# IP5568-MCU-188-3LED-ACL-V1_0.net
KiCad netlist of a schematic drawn in Altium Designer
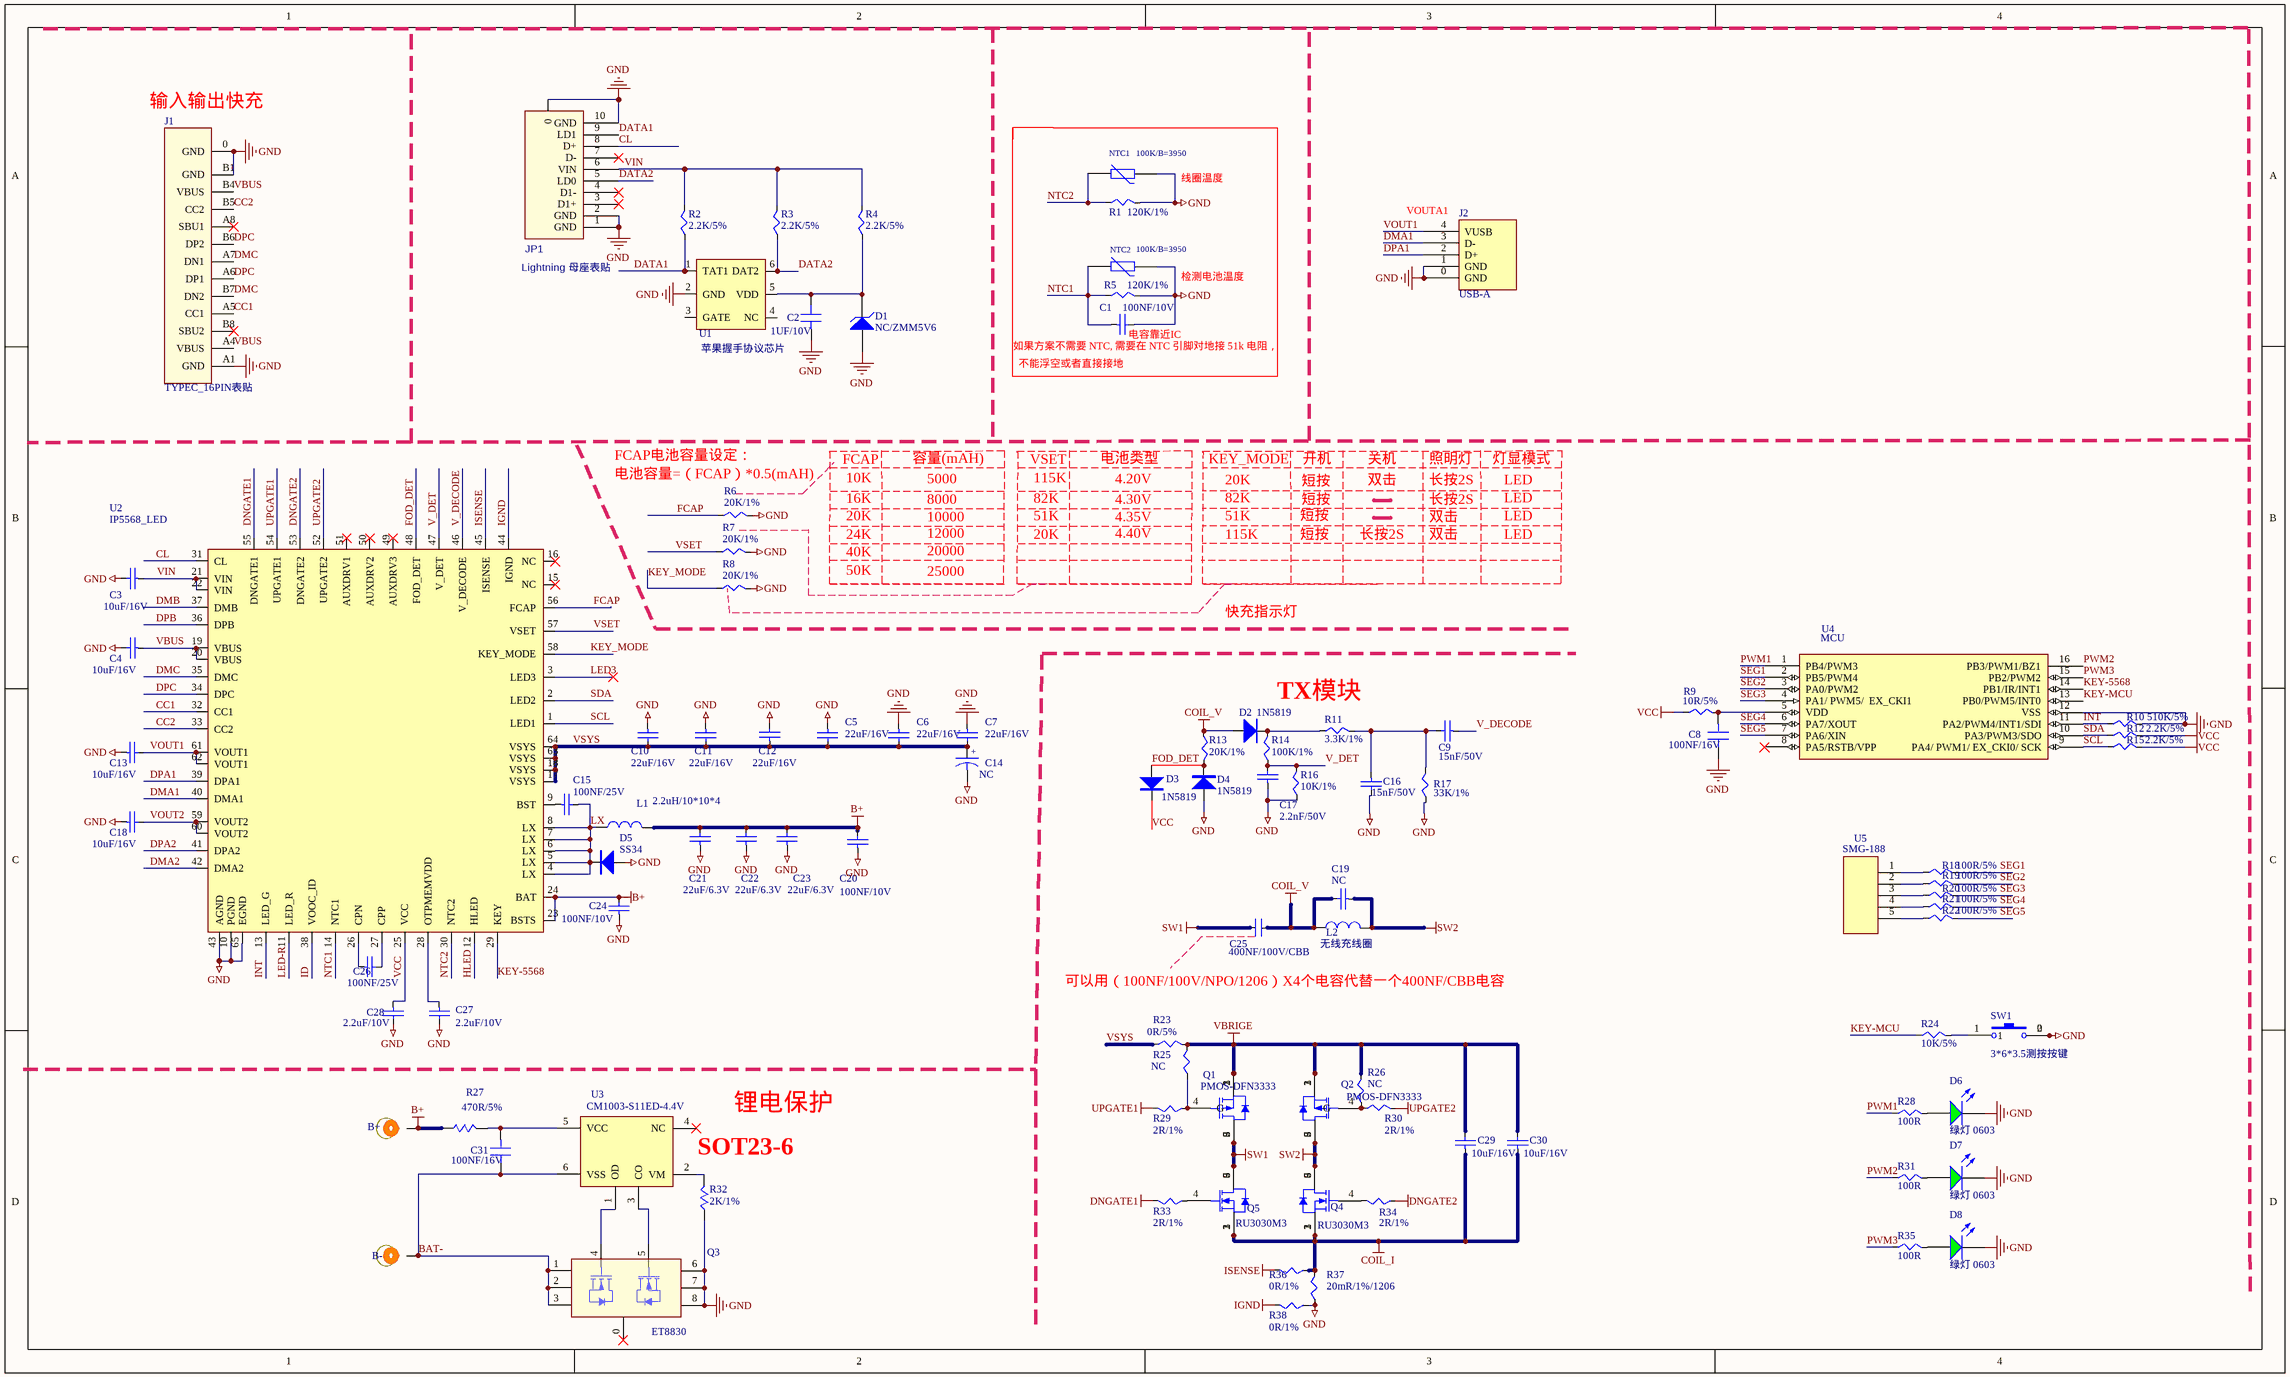
[diagram p0: IP5568-MCU-188-3LED-ACL-V1.0.SchDoc]

(export (version "E")
  (design (tool "Eeschema 10.0.6"))
  (components
    (comp (ref "B+")
      (value "BAT+")
      (footprint "BAT-3X3")
      (libsource (lib "nagg_zhang20201228") (part "BAT+"))
    )
    (comp (ref "B-")
      (value "BAT-")
      (footprint "BAT-3X3")
      (libsource (lib "nagg_zhang20201228") (part "BAT-"))
    )
    (comp (ref "C1")
      (value "100NF/10V")
      (footprint "0402C")
      (description "Capacitor")
      (libsource (lib "A") (part "CAP"))
    )
    (comp (ref "C2")
      (value "1UF/10V")
      (footprint "0402C")
      (libsource (lib "nagg_zhang20201228") (part "CAP-0603"))
    )
    (comp (ref "C3")
      (value "10uF/16V")
      (footprint "C0805")
      (description "Capacitor")
      (libsource (lib "A") (part "CAP"))
    )
    (comp (ref "C4")
      (value "10uF/16V")
      (footprint "C0805")
      (description "Capacitor")
      (libsource (lib "A") (part "CAP"))
    )
    (comp (ref "C5")
      (value "22uF/16V")
      (footprint "C0805")
      (description "Capacitor")
      (libsource (lib "A") (part "CAP"))
    )
    (comp (ref "C6")
      (value "22uF/16V")
      (footprint "C0805")
      (description "Capacitor")
      (libsource (lib "A") (part "CAP"))
    )
    (comp (ref "C7")
      (value "22uF/16V")
      (footprint "C0805")
      (description "Capacitor")
      (libsource (lib "A") (part "CAP"))
    )
    (comp (ref "C8")
      (value "100NF/16V")
      (footprint "0402C")
      (libsource (lib "nagg_zhang20201228") (part "CAP-0603"))
    )
    (comp (ref "C9")
      (value "15nF/50V")
      (footprint "0402C")
      (description "Capacitor")
      (libsource (lib "A") (part "CAP"))
    )
    (comp (ref "C10")
      (value "22uF/16V")
      (footprint "C0805")
      (description "Capacitor")
      (libsource (lib "A") (part "CAP"))
    )
    (comp (ref "C11")
      (value "22uF/16V")
      (footprint "C0805")
      (description "Capacitor")
      (libsource (lib "A") (part "CAP"))
    )
    (comp (ref "C12")
      (value "22uF/16V")
      (footprint "C0805")
      (description "Capacitor")
      (libsource (lib "A") (part "CAP"))
    )
    (comp (ref "C13")
      (value "10uF/16V")
      (footprint "C0805")
      (description "Capacitor")
      (libsource (lib "A") (part "CAP"))
    )
    (comp (ref "C14")
      (value "NC")
      (footprint "CAP-6.3X8-P2.5-S1")
      (description "Capacitor")
      (libsource (lib "A") (part "CAPACITOR POL"))
    )
    (comp (ref "C15")
      (value "100NF/25V")
      (footprint "0402C")
      (description "Capacitor")
      (libsource (lib "A") (part "CAP"))
    )
    (comp (ref "C16")
      (value "15nF/50V")
      (footprint "0402C")
      (description "Capacitor")
      (libsource (lib "A") (part "CAP"))
    )
    (comp (ref "C17")
      (value "2.2nF/50V")
      (footprint "0402C")
      (description "Capacitor")
      (libsource (lib "A") (part "CAP"))
    )
    (comp (ref "C18")
      (value "10uF/16V")
      (footprint "C0805")
      (description "Capacitor")
      (libsource (lib "A") (part "CAP"))
    )
    (comp (ref "C19")
      (value "NC")
      (footprint "0402C")
      (description "Capacitor")
      (libsource (lib "A") (part "CAP"))
    )
    (comp (ref "C20")
      (value "100NF/10V")
      (footprint "0402C")
      (description "Capacitor")
      (libsource (lib "A") (part "CAP"))
    )
    (comp (ref "C21")
      (value "22uF/6.3V")
      (footprint "C0805")
      (description "Capacitor")
      (libsource (lib "A") (part "CAP"))
    )
    (comp (ref "C22")
      (value "22uF/6.3V")
      (footprint "C0805")
      (description "Capacitor")
      (libsource (lib "A") (part "CAP"))
    )
    (comp (ref "C23")
      (value "22uF/6.3V")
      (footprint "C0805")
      (description "Capacitor")
      (libsource (lib "A") (part "CAP"))
    )
    (comp (ref "C24")
      (value "100NF/10V")
      (footprint "0402C")
      (description "Capacitor")
      (libsource (lib "A") (part "CAP"))
    )
    (comp (ref "C25")
      (value "400NF/100V/CBB")
      (footprint "CAP-CBB-404 100V")
      (description "Capacitor")
      (libsource (lib "") (part "CAP_1"))
    )
    (comp (ref "C26")
      (value "100NF/25V")
      (footprint "0402C")
      (description "Capacitor")
      (libsource (lib "A") (part "CAP"))
    )
    (comp (ref "C27")
      (value "2.2uF/10V")
      (footprint "0603C")
      (description "Capacitor")
      (libsource (lib "A") (part "CAP"))
    )
    (comp (ref "C28")
      (value "2.2uF/10V")
      (footprint "0603C")
      (description "Capacitor")
      (libsource (lib "A") (part "CAP"))
    )
    (comp (ref "C29")
      (value "10uF/16V")
      (footprint "C0805")
      (description "Capacitor")
      (libsource (lib "A") (part "CAP"))
    )
    (comp (ref "C30")
      (value "10uF/16V")
      (footprint "C0805")
      (description "Capacitor")
      (libsource (lib "A") (part "CAP"))
    )
    (comp (ref "C31")
      (value "100NF/16V")
      (footprint "0402C")
      (libsource (lib "nagg_zhang20201228") (part "CAP-0603"))
    )
    (comp (ref "D1")
      (value "NC/ZMM5V6")
      (footprint "SOD-123")
      (description "稳压二极管")
      (libsource (lib "Zener") (part "LL-34 ZMM5V6"))
    )
    (comp (ref "D2")
      (value "1N5819")
      (footprint "SOD-323")
      (description "Diode")
      (libsource (lib "A") (part "DIODE"))
    )
    (comp (ref "D3")
      (value "1N5819")
      (footprint "SOD-323")
      (description "Diode")
      (libsource (lib "A") (part "DIODE"))
    )
    (comp (ref "D4")
      (value "1N5819")
      (footprint "SOD-323")
      (description "Diode")
      (libsource (lib "A") (part "DIODE"))
    )
    (comp (ref "D5")
      (value "SS34")
      (footprint "SMA")
      (description "Diode")
      (libsource (lib "") (part "DIODE_1"))
    )
    (comp (ref "D6")
      (value "绿灯 0603")
      (footprint "LC-0603_LED_S1")
      (description "发光二极管")
      (libsource (lib "LED") (part "0603 绿灯"))
    )
    (comp (ref "D7")
      (value "绿灯 0603")
      (footprint "LC-0603_LED_S1")
      (description "发光二极管")
      (libsource (lib "LED") (part "0603 绿灯"))
    )
    (comp (ref "D8")
      (value "绿灯 0603")
      (footprint "LC-0603_LED_S1")
      (description "发光二极管")
      (libsource (lib "LED") (part "0603 绿灯"))
    )
    (comp (ref "J1")
      (value "TYPEC_16PIN表贴")
      (footprint "TYPE C 2.0-16pin 表贴")
      (libsource (lib "AD09-POWER BANK") (part "TYPEC_16PIN表贴"))
    )
    (comp (ref "J2")
      (value "USB-A")
      (footprint "USB-AF8.5沉板1.9前插后贴")
      (libsource (lib "AD09-POWER BANK") (part "USB--A-4PIN"))
    )
    (comp (ref "JP1")
      (value "Lightning 母座表贴")
      (footprint "Lightning_10")
      (libsource (lib "AD09-POWER BANK") (part "Lightning 母座表贴"))
    )
    (comp (ref "L1")
      (value "2.2uH/10*10*4")
      (footprint "L1040")
      (description "电感")
      (libsource (lib "A") (part "INDUCTOR"))
    )
    (comp (ref "L2")
      (value "无线充线圈")
      (footprint "2P-2.5L")
      (description "电感")
      (libsource (lib "A") (part "INDUCTOR"))
    )
    (comp (ref "NTC1")
      (value "100K/B=3950")
      (footprint "NTC-插件")
      (description "温敏电阻")
      (libsource (lib "AD09-POWER BANK") (part "NTC"))
    )
    (comp (ref "NTC2")
      (value "100K/B=3950")
      (footprint "NTC-插件")
      (description "温敏电阻")
      (libsource (lib "AD09-POWER BANK") (part "NTC"))
    )
    (comp (ref "Q1")
      (value "PMOS-DFN3333")
      (footprint "PDFN3333-8_L3.1-W3.2-P0.65-LS3.4-BL")
      (libsource (lib "AD09-POWER BANK") (part "PMOS-DFN3333_1"))
    )
    (comp (ref "Q2")
      (value "PMOS-DFN3333")
      (footprint "PDFN3333-8_L3.1-W3.2-P0.65-LS3.4-BL")
      (libsource (lib "AD09-POWER BANK") (part "PMOS-DFN3333_1"))
    )
    (comp (ref "Q3")
      (value "ET8830")
      (footprint "ET-8830-DFN3x3-8L")
      (description "NMOS-DUAL-N")
      (libsource (lib "AD09-POWER BANK") (part "NMOS-ET8830-DFN3333"))
    )
    (comp (ref "Q4")
      (value "RU3030M3")
      (footprint "PDFN3333-8_L3.1-W3.2-P0.65-LS3.4-BL")
      (description "NMOS-DFN3333")
      (libsource (lib "AD09-POWER BANK") (part "NMOS-DFN3333"))
    )
    (comp (ref "Q5")
      (value "RU3030M3")
      (footprint "PDFN3333-8_L3.1-W3.2-P0.65-LS3.4-BL")
      (description "NMOS-DFN3333")
      (libsource (lib "AD09-POWER BANK") (part "NMOS-DFN3333"))
    )
    (comp (ref "R1") (value "120K/1%") (footprint "0402R") (libsource (lib "A") (part "RES1")))
    (comp (ref "R2") (value "2.2K/5%") (footprint "0402R") (libsource (lib "A") (part "RES1")))
    (comp (ref "R3") (value "2.2K/5%") (footprint "0402R") (libsource (lib "A") (part "RES1")))
    (comp (ref "R4") (value "2.2K/5%") (footprint "0402R") (libsource (lib "A") (part "RES1")))
    (comp (ref "R5") (value "120K/1%") (footprint "0402R") (libsource (lib "A") (part "RES1")))
    (comp (ref "R6") (value "20K/1%") (footprint "0402R") (libsource (lib "A") (part "RES1")))
    (comp (ref "R7") (value "20K/1%") (footprint "0402R") (libsource (lib "A") (part "RES1")))
    (comp (ref "R8") (value "20K/1%") (footprint "0402R") (libsource (lib "A") (part "RES1")))
    (comp (ref "R9") (value "10R/5%") (footprint "0603R") (libsource (lib "A") (part "RES1")))
    (comp (ref "R10") (value "510K/5%") (footprint "0402R") (libsource (lib "A") (part "RES1")))
    (comp (ref "R11") (value "3.3K/1%") (footprint "0402R") (libsource (lib "A") (part "RES1")))
    (comp (ref "R12") (value "2.2K/5%") (footprint "0402R") (libsource (lib "A") (part "RES1")))
    (comp (ref "R13") (value "20K/1%") (footprint "0402R") (libsource (lib "A") (part "RES1")))
    (comp (ref "R14") (value "100K/1%") (footprint "0402R") (libsource (lib "A") (part "RES1")))
    (comp (ref "R15") (value "2.2K/5%") (footprint "0402R") (libsource (lib "A") (part "RES1")))
    (comp (ref "R16") (value "10K/1%") (footprint "0402R") (libsource (lib "A") (part "RES1")))
    (comp (ref "R17") (value "33K/1%") (footprint "0402R") (libsource (lib "A") (part "RES1")))
    (comp (ref "R18") (value "100R/5%") (footprint "0402R") (libsource (lib "A") (part "RES1")))
    (comp (ref "R19") (value "100R/5%") (footprint "0402R") (libsource (lib "A") (part "RES1")))
    (comp (ref "R20") (value "100R/5%") (footprint "0402R") (libsource (lib "A") (part "RES1")))
    (comp (ref "R21") (value "100R/5%") (footprint "0402R") (libsource (lib "A") (part "RES1")))
    (comp (ref "R22") (value "100R/5%") (footprint "0402R") (libsource (lib "A") (part "RES1")))
    (comp (ref "R23") (value "0R/5%") (footprint "0805") (libsource (lib "A") (part "RES1")))
    (comp (ref "R24") (value "10K/5%") (footprint "0402R") (libsource (lib "A") (part "RES1")))
    (comp (ref "R25") (value "NC") (footprint "0402R") (libsource (lib "A") (part "RES1")))
    (comp (ref "R26") (value "NC") (footprint "0402R") (libsource (lib "A") (part "RES1")))
    (comp (ref "R27")
      (value "470R/5%")
      (footprint "0402R")
      (libsource (lib "nagg_zhang20201228") (part "RES-0603"))
    )
    (comp (ref "R28") (value "100R") (footprint "0402R") (libsource (lib "A") (part "RES1")))
    (comp (ref "R29") (value "2R/1%") (footprint "0402R") (libsource (lib "A") (part "RES1")))
    (comp (ref "R30") (value "2R/1%") (footprint "0402R") (libsource (lib "A") (part "RES1")))
    (comp (ref "R31") (value "100R") (footprint "0402R") (libsource (lib "A") (part "RES1")))
    (comp (ref "R32")
      (value "2K/1%")
      (footprint "0402R")
      (libsource (lib "nagg_zhang20201228") (part "RES-0603"))
    )
    (comp (ref "R33") (value "2R/1%") (footprint "0402R") (libsource (lib "A") (part "RES1")))
    (comp (ref "R34") (value "2R/1%") (footprint "0402R") (libsource (lib "A") (part "RES1")))
    (comp (ref "R35") (value "100R") (footprint "0402R") (libsource (lib "A") (part "RES1")))
    (comp (ref "R36") (value "0R/1%") (footprint "0402R") (libsource (lib "A") (part "RES1")))
    (comp (ref "R37") (value "20mR/1%/1206") (footprint "1206") (libsource (lib "A") (part "RES1")))
    (comp (ref "R38") (value "0R/1%") (footprint "0402R") (libsource (lib "A") (part "RES1")))
    (comp (ref "SW1")
      (value "3*6*3.5测按按键")
      (footprint "SW-3X6X3.5mm-定位柱0.7-通孔")
      (description "侧按按键")
      (fields (field (name "PUBLISHER") "Altium Limited"))
      (libsource (lib "AD09-POWER BANK") (part "KEY-3*6*3.5mm"))
    )
    (comp (ref "U1") (value "苹果握手协议芯片") (footprint "SOT23-6") (libsource (lib "A") (part "LP05")))
    (comp (ref "U2")
      (value "IP5568_LED")
      (footprint "QFN64-8*8-0.4")
      (description "移动电源快充+无线充快充TX/RX")
      (libsource (lib "A") (part "IP5568"))
    )
    (comp (ref "U3")
      (value "CM1003-S11ED-4.4V")
      (footprint "SOT23-6")
      (description "锂电保护芯片")
      (libsource (lib "AD09-POWER BANK") (part "CM1003"))
    )
    (comp (ref "U4")
      (value "MCU")
      (footprint "SOP16L")
      (libsource (lib "AD09-POWER BANK") (part "MCU_NY8A054E"))
    )
    (comp (ref "U5")
      (value "SMG-188")
      (footprint "SMG-188-CYZ2342-5-75BWGD")
      (libsource (lib "AD09-POWER BANK") (part "SMG-188-YFT1508SWPGAD-5D-1"))
    )
  )
  (nets
    (net (code "1") (name "/BAT-") (class "Default")
      (node (ref "B-") (pin "1") (pinfunction "1_1") (pintype "passive"))
      (node (ref "C31") (pin "2") (pinfunction "2_2") (pintype "passive"))
      (node (ref "Q3") (pin "1") (pinfunction "S1_1") (pintype "passive"))
      (node (ref "Q3") (pin "2") (pinfunction "S1_2") (pintype "passive"))
      (node (ref "Q3") (pin "3") (pinfunction "S1_3") (pintype "passive"))
      (node (ref "U3") (pin "6") (pinfunction "VSS_6") (pintype "passive"))
    )
    (net (code "2") (name "/CC1") (class "Default")
      (node (ref "J1") (pin "A5") (pinfunction "CC1_A5") (pintype "passive"))
      (node (ref "U2") (pin "32") (pinfunction "CC1_32") (pintype "passive"))
    )
    (net (code "3") (name "/CC2") (class "Default")
      (node (ref "J1") (pin "B5") (pinfunction "CC2_B5") (pintype "passive"))
      (node (ref "U2") (pin "33") (pinfunction "CC2_33") (pintype "passive"))
    )
    (net (code "4") (name "/CL") (class "Default")
      (node (ref "JP1") (pin "8") (pinfunction "D+_8") (pintype "passive"))
      (node (ref "U2") (pin "31") (pinfunction "CL_31") (pintype "passive"))
    )
    (net (code "5") (name "/DATA1") (class "Default")
      (node (ref "JP1") (pin "9") (pinfunction "LD1_9") (pintype "passive"))
      (node (ref "R2") (pin "1") (pinfunction "1_1") (pintype "passive"))
      (node (ref "U1") (pin "1") (pinfunction "TAT1_1") (pintype "passive"))
    )
    (net (code "6") (name "/DATA2") (class "Default")
      (node (ref "JP1") (pin "5") (pinfunction "LD0_5") (pintype "passive"))
      (node (ref "R3") (pin "1") (pinfunction "1_1") (pintype "passive"))
      (node (ref "U1") (pin "6") (pinfunction "DAT2_6") (pintype "passive"))
    )
    (net (code "7") (name "/DMA1") (class "Default")
      (node (ref "J2") (pin "3") (pinfunction "D-_3") (pintype "passive"))
      (node (ref "U2") (pin "40") (pinfunction "DMA1_40") (pintype "passive"))
    )
    (net (code "8") (name "/DMA2") (class "Default")
      (node (ref "U2") (pin "42") (pinfunction "DMA2_42") (pintype "passive"))
    )
    (net (code "9") (name "/DMB") (class "Default")
      (node (ref "U2") (pin "37") (pinfunction "DMB_37") (pintype "passive"))
    )
    (net (code "10") (name "/DMC") (class "Default")
      (node (ref "J1") (pin "A7") (pinfunction "DN1_A7") (pintype "passive"))
      (node (ref "J1") (pin "B7") (pinfunction "DN2_B7") (pintype "passive"))
      (node (ref "U2") (pin "35") (pinfunction "DMC_35") (pintype "passive"))
    )
    (net (code "11") (name "/DPA1") (class "Default")
      (node (ref "J2") (pin "2") (pinfunction "D+_2") (pintype "passive"))
      (node (ref "U2") (pin "39") (pinfunction "DPA1_39") (pintype "passive"))
    )
    (net (code "12") (name "/DPA2") (class "Default")
      (node (ref "U2") (pin "41") (pinfunction "DPA2_41") (pintype "passive"))
    )
    (net (code "13") (name "/DPB") (class "Default")
      (node (ref "U2") (pin "36") (pinfunction "DPB_36") (pintype "passive"))
    )
    (net (code "14") (name "/DPC") (class "Default")
      (node (ref "J1") (pin "A6") (pinfunction "DP1_A6") (pintype "passive"))
      (node (ref "J1") (pin "B6") (pinfunction "DP2_B6") (pintype "passive"))
      (node (ref "U2") (pin "34") (pinfunction "DPC_34") (pintype "passive"))
    )
    (net (code "15") (name "/FCAP") (class "Default")
      (node (ref "R6") (pin "1") (pinfunction "1_1") (pintype "passive"))
      (node (ref "U2") (pin "56") (pinfunction "FCAP_56") (pintype "passive"))
    )
    (net (code "16") (name "/FOD_DET") (class "Default")
      (node (ref "D3") (pin "A") (pinfunction "A_A") (pintype "passive"))
      (node (ref "D4") (pin "K") (pinfunction "K_K") (pintype "passive"))
      (node (ref "R13") (pin "2") (pinfunction "2_2") (pintype "passive"))
      (node (ref "U2") (pin "48") (pinfunction "FOD_DET_48") (pintype "passive"))
    )
    (net (code "17") (name "/HLED") (class "Default")
      (node (ref "U2") (pin "12") (pinfunction "HLED_12") (pintype "passive"))
    )
    (net (code "18") (name "/ID") (class "Default")
      (node (ref "U2") (pin "38") (pinfunction "VOOC_ID_38") (pintype "passive"))
    )
    (net (code "19") (name "/INT") (class "Default")
      (node (ref "R10") (pin "1") (pinfunction "1_1") (pintype "passive"))
      (node (ref "U2") (pin "13") (pinfunction "LED_G_13") (pintype "passive"))
      (node (ref "U4") (pin "11") (pinfunction "PA2/PWM4/INT1/SDI_11") (pintype "bidirectional"))
    )
    (net (code "20") (name "/KEY-5568") (class "Default")
      (node (ref "U2") (pin "29") (pinfunction "KEY_29") (pintype "passive"))
      (node (ref "U4") (pin "14") (pinfunction "PB1/IR/INT1_14") (pintype "bidirectional"))
    )
    (net (code "21") (name "/KEY-MCU") (class "Default")
      (node (ref "R24") (pin "1") (pinfunction "1_1") (pintype "passive"))
      (node (ref "U4") (pin "13") (pinfunction "PB0/PWM5/INT0_13") (pintype "bidirectional"))
    )
    (net (code "22") (name "/KEY_MODE") (class "Default")
      (node (ref "R8") (pin "1") (pinfunction "1_1") (pintype "passive"))
      (node (ref "U2") (pin "58") (pinfunction "KEY_MODE_58") (pintype "passive"))
    )
    (net (code "23") (name "/LED-R") (class "Default")
      (node (ref "U2") (pin "11") (pinfunction "LED_R_11") (pintype "passive"))
    )
    (net (code "24") (name "/LED3") (class "Default")
      (node (ref "U2") (pin "3") (pinfunction "LED3_3") (pintype "passive+no_connect"))
    )
    (net (code "25") (name "/LX") (class "Default")
      (node (ref "C15") (pin "2") (pinfunction "2_2") (pintype "passive"))
      (node (ref "D5") (pin "2") (pinfunction "2_2") (pintype "passive"))
      (node (ref "L1") (pin "1") (pinfunction "1_1") (pintype "passive"))
      (node (ref "U2") (pin "4") (pinfunction "LX_4") (pintype "passive"))
      (node (ref "U2") (pin "5") (pinfunction "LX_5") (pintype "passive"))
      (node (ref "U2") (pin "6") (pinfunction "LX_6") (pintype "passive"))
      (node (ref "U2") (pin "7") (pinfunction "LX_7") (pintype "passive"))
      (node (ref "U2") (pin "8") (pinfunction "LX_8") (pintype "passive"))
    )
    (net (code "26") (name "/NTC1") (class "Default")
      (node (ref "C1") (pin "1") (pinfunction "1_1") (pintype "passive"))
      (node (ref "NTC2") (pin "1") (pinfunction "1_1") (pintype "passive"))
      (node (ref "R5") (pin "1") (pinfunction "1_1") (pintype "passive"))
      (node (ref "U2") (pin "14") (pinfunction "NTC1_14") (pintype "passive"))
    )
    (net (code "27") (name "/NTC2") (class "Default")
      (node (ref "NTC1") (pin "1") (pinfunction "1_1") (pintype "passive"))
      (node (ref "R1") (pin "1") (pinfunction "1_1") (pintype "passive"))
      (node (ref "U2") (pin "30") (pinfunction "NTC2_30") (pintype "passive"))
    )
    (net (code "28") (name "/PWM1") (class "Default")
      (node (ref "R28") (pin "1") (pinfunction "1_1") (pintype "passive"))
      (node (ref "U4") (pin "1") (pinfunction "PB4/PWM3_1") (pintype "power_in"))
    )
    (net (code "29") (name "/PWM2") (class "Default")
      (node (ref "R31") (pin "1") (pinfunction "1_1") (pintype "passive"))
      (node (ref "U4") (pin "16") (pinfunction "PB3/PWM1/BZ1_16") (pintype "power_in"))
    )
    (net (code "30") (name "/PWM3") (class "Default")
      (node (ref "R35") (pin "1") (pinfunction "1_1") (pintype "passive"))
      (node (ref "U4") (pin "15") (pinfunction "PB2/PWM2_15") (pintype "bidirectional"))
    )
    (net (code "31") (name "/SCL") (class "Default")
      (node (ref "R15") (pin "1") (pinfunction "1_1") (pintype "passive"))
      (node (ref "U2") (pin "1") (pinfunction "LED1_1") (pintype "passive"))
      (node (ref "U4") (pin "9") (pinfunction "PA4/_PWM1/_EX_CKI0/_SCK_9") (pintype "bidirectional"))
    )
    (net (code "32") (name "/SDA") (class "Default")
      (node (ref "R12") (pin "1") (pinfunction "1_1") (pintype "passive"))
      (node (ref "U2") (pin "2") (pinfunction "LED2_2") (pintype "passive"))
      (node (ref "U4") (pin "10") (pinfunction "PA3/PWM3/SDO_10") (pintype "bidirectional"))
    )
    (net (code "33") (name "/SEG1") (class "Default")
      (node (ref "R18") (pin "2") (pinfunction "2_2") (pintype "passive"))
      (node (ref "U4") (pin "2") (pinfunction "PB5/PWM4_2") (pintype "bidirectional"))
    )
    (net (code "34") (name "/SEG2") (class "Default")
      (node (ref "R19") (pin "2") (pinfunction "2_2") (pintype "passive"))
      (node (ref "U4") (pin "3") (pinfunction "PA0/PWM2_3") (pintype "bidirectional"))
    )
    (net (code "35") (name "/SEG3") (class "Default")
      (node (ref "R20") (pin "2") (pinfunction "2_2") (pintype "passive"))
      (node (ref "U4") (pin "4") (pinfunction "PA1/_PWM5/__EX_CKI1_4") (pintype "input"))
    )
    (net (code "36") (name "/SEG4") (class "Default")
      (node (ref "R21") (pin "2") (pinfunction "2_2") (pintype "passive"))
      (node (ref "U4") (pin "6") (pinfunction "PA7/XOUT_6") (pintype "bidirectional"))
    )
    (net (code "37") (name "/SEG5") (class "Default")
      (node (ref "R22") (pin "2") (pinfunction "2_2") (pintype "passive"))
      (node (ref "U4") (pin "7") (pinfunction "PA6/XIN_7") (pintype "bidirectional"))
    )
    (net (code "38") (name "/VBUS") (class "Default")
      (node (ref "C4") (pin "1") (pinfunction "1_1") (pintype "passive"))
      (node (ref "J1") (pin "A4") (pinfunction "VBUS_A4") (pintype "passive"))
      (node (ref "J1") (pin "B4") (pinfunction "VBUS_B4") (pintype "passive"))
      (node (ref "U2") (pin "19") (pinfunction "VBUS_19") (pintype "passive"))
      (node (ref "U2") (pin "20") (pinfunction "VBUS_20") (pintype "passive"))
    )
    (net (code "39") (name "/VIN") (class "Default")
      (node (ref "C3") (pin "1") (pinfunction "1_1") (pintype "passive"))
      (node (ref "JP1") (pin "6") (pinfunction "VIN_6") (pintype "passive"))
      (node (ref "R2") (pin "2") (pinfunction "2_2") (pintype "passive"))
      (node (ref "R3") (pin "2") (pinfunction "2_2") (pintype "passive"))
      (node (ref "R4") (pin "2") (pinfunction "2_2") (pintype "passive"))
      (node (ref "U2") (pin "21") (pinfunction "VIN_21") (pintype "passive"))
      (node (ref "U2") (pin "22") (pinfunction "VIN_22") (pintype "passive"))
    )
    (net (code "40") (name "/VOUT1") (class "Default")
      (node (ref "C13") (pin "2") (pinfunction "2_2") (pintype "passive"))
      (node (ref "J2") (pin "4") (pinfunction "VUSB_4") (pintype "passive"))
      (node (ref "U2") (pin "61") (pinfunction "VOUT1_61") (pintype "passive"))
      (node (ref "U2") (pin "62") (pinfunction "VOUT1_62") (pintype "passive"))
    )
    (net (code "41") (name "/VOUT2") (class "Default")
      (node (ref "C18") (pin "2") (pinfunction "2_2") (pintype "passive"))
      (node (ref "U2") (pin "59") (pinfunction "VOUT2_59") (pintype "passive"))
      (node (ref "U2") (pin "60") (pinfunction "VOUT2_60") (pintype "passive"))
    )
    (net (code "42") (name "/VSET") (class "Default")
      (node (ref "R7") (pin "1") (pinfunction "1_1") (pintype "passive"))
      (node (ref "U2") (pin "57") (pinfunction "VSET_57") (pintype "passive"))
    )
    (net (code "43") (name "/VSYS") (class "Default")
      (node (ref "C10") (pin "2") (pinfunction "2_2") (pintype "passive"))
      (node (ref "C11") (pin "2") (pinfunction "2_2") (pintype "passive"))
      (node (ref "C12") (pin "1") (pinfunction "1_1") (pintype "passive"))
      (node (ref "C14") (pin "1") (pinfunction "1_1") (pintype "passive"))
      (node (ref "C5") (pin "2") (pinfunction "2_2") (pintype "passive"))
      (node (ref "C6") (pin "2") (pinfunction "2_2") (pintype "passive"))
      (node (ref "C7") (pin "2") (pinfunction "2_2") (pintype "passive"))
      (node (ref "R23") (pin "1") (pinfunction "1_1") (pintype "passive"))
      (node (ref "U2") (pin "17") (pinfunction "VSYS_17") (pintype "passive"))
      (node (ref "U2") (pin "18") (pinfunction "VSYS_18") (pintype "passive"))
      (node (ref "U2") (pin "63") (pinfunction "VSYS_63") (pintype "passive"))
      (node (ref "U2") (pin "64") (pinfunction "VSYS_64") (pintype "passive"))
    )
    (net (code "44") (name "/V_DECODE") (class "Default")
      (node (ref "C9") (pin "1") (pinfunction "1_1") (pintype "passive"))
      (node (ref "U2") (pin "46") (pinfunction "V_DECODE_46") (pintype "passive"))
    )
    (net (code "45") (name "/V_DET") (class "Default")
      (node (ref "C17") (pin "2") (pinfunction "2_2") (pintype "passive"))
      (node (ref "R14") (pin "1") (pinfunction "1_1") (pintype "passive"))
      (node (ref "R16") (pin "2") (pinfunction "2_2") (pintype "passive"))
      (node (ref "U2") (pin "47") (pinfunction "V_DET_47") (pintype "passive"))
    )
    (net (code "46") (name "B+") (class "Default")
      (node (ref "B+") (pin "1") (pinfunction "1_1") (pintype "passive"))
      (node (ref "C20") (pin "2") (pinfunction "2_2") (pintype "passive"))
      (node (ref "C21") (pin "2") (pinfunction "2_2") (pintype "passive"))
      (node (ref "C22") (pin "2") (pinfunction "2_2") (pintype "passive"))
      (node (ref "C23") (pin "2") (pinfunction "2_2") (pintype "passive"))
      (node (ref "C24") (pin "2") (pinfunction "2_2") (pintype "passive"))
      (node (ref "L1") (pin "2") (pinfunction "2_2") (pintype "passive"))
      (node (ref "R27") (pin "1") (pinfunction "1_1") (pintype "passive"))
      (node (ref "U2") (pin "23") (pinfunction "BSTS_23") (pintype "passive"))
      (node (ref "U2") (pin "24") (pinfunction "BAT_24") (pintype "passive"))
    )
    (net (code "47") (name "COIL_I") (class "Default")
      (node (ref "C29") (pin "1") (pinfunction "1_1") (pintype "passive"))
      (node (ref "C30") (pin "1") (pinfunction "1_1") (pintype "passive"))
      (node (ref "Q4") (pin "1") (pinfunction "S_1") (pintype "passive"))
      (node (ref "Q4") (pin "2") (pinfunction "S_2") (pintype "passive"))
      (node (ref "Q4") (pin "3") (pinfunction "S_3") (pintype "passive"))
      (node (ref "Q5") (pin "1") (pinfunction "S_1") (pintype "passive"))
      (node (ref "Q5") (pin "2") (pinfunction "S_2") (pintype "passive"))
      (node (ref "Q5") (pin "3") (pinfunction "S_3") (pintype "passive"))
      (node (ref "R36") (pin "1") (pinfunction "1_1") (pintype "passive"))
      (node (ref "R37") (pin "2") (pinfunction "2_2") (pintype "passive"))
    )
    (net (code "48") (name "COIL_V") (class "Default")
      (node (ref "C19") (pin "2") (pinfunction "2_2") (pintype "passive"))
      (node (ref "C25") (pin "2") (pinfunction "2_2") (pintype "passive"))
      (node (ref "D2") (pin "A") (pinfunction "A_A") (pintype "passive"))
      (node (ref "L2") (pin "1") (pinfunction "1_1") (pintype "passive"))
      (node (ref "R13") (pin "1") (pinfunction "1_1") (pintype "passive"))
    )
    (net (code "49") (name "DNGATE1") (class "Default")
      (node (ref "R33") (pin "2") (pinfunction "2_2") (pintype "passive"))
      (node (ref "U2") (pin "55") (pinfunction "DNGATE1_55") (pintype "passive"))
    )
    (net (code "50") (name "DNGATE2") (class "Default")
      (node (ref "R34") (pin "1") (pinfunction "1_1") (pintype "passive"))
      (node (ref "U2") (pin "53") (pinfunction "DNGATE2_53") (pintype "passive"))
    )
    (net (code "51") (name "GND") (class "Default")
      (node (ref "C1") (pin "2") (pinfunction "2_2") (pintype "passive"))
      (node (ref "C10") (pin "1") (pinfunction "1_1") (pintype "passive"))
      (node (ref "C11") (pin "1") (pinfunction "1_1") (pintype "passive"))
      (node (ref "C12") (pin "2") (pinfunction "2_2") (pintype "passive"))
      (node (ref "C13") (pin "1") (pinfunction "1_1") (pintype "passive"))
      (node (ref "C14") (pin "2") (pinfunction "2_2") (pintype "passive"))
      (node (ref "C16") (pin "2") (pinfunction "2_2") (pintype "passive"))
      (node (ref "C17") (pin "1") (pinfunction "1_1") (pintype "passive"))
      (node (ref "C18") (pin "1") (pinfunction "1_1") (pintype "passive"))
      (node (ref "C2") (pin "1") (pinfunction "1_1") (pintype "passive"))
      (node (ref "C20") (pin "1") (pinfunction "1_1") (pintype "passive"))
      (node (ref "C21") (pin "1") (pinfunction "1_1") (pintype "passive"))
      (node (ref "C22") (pin "1") (pinfunction "1_1") (pintype "passive"))
      (node (ref "C23") (pin "1") (pinfunction "1_1") (pintype "passive"))
      (node (ref "C24") (pin "1") (pinfunction "1_1") (pintype "passive"))
      (node (ref "C27") (pin "2") (pinfunction "2_2") (pintype "passive"))
      (node (ref "C28") (pin "2") (pinfunction "2_2") (pintype "passive"))
      (node (ref "C3") (pin "2") (pinfunction "2_2") (pintype "passive"))
      (node (ref "C4") (pin "2") (pinfunction "2_2") (pintype "passive"))
      (node (ref "C5") (pin "1") (pinfunction "1_1") (pintype "passive"))
      (node (ref "C6") (pin "1") (pinfunction "1_1") (pintype "passive"))
      (node (ref "C7") (pin "1") (pinfunction "1_1") (pintype "passive"))
      (node (ref "C8") (pin "2") (pinfunction "2_2") (pintype "passive"))
      (node (ref "D1") (pin "1") (pinfunction "A_1") (pintype "passive"))
      (node (ref "D4") (pin "A") (pinfunction "A_A") (pintype "passive"))
      (node (ref "D5") (pin "1") (pinfunction "1_1") (pintype "passive"))
      (node (ref "D6") (pin "K") (pinfunction "K_K") (pintype "passive"))
      (node (ref "D7") (pin "K") (pinfunction "K_K") (pintype "passive"))
      (node (ref "D8") (pin "K") (pinfunction "K_K") (pintype "passive"))
      (node (ref "J1") (pin "0") (pinfunction "GND_0") (pintype "passive"))
      (node (ref "J1") (pin "A1") (pinfunction "GND_A1") (pintype "passive"))
      (node (ref "J1") (pin "B1") (pinfunction "GND_B1") (pintype "passive"))
      (node (ref "J2") (pin "0") (pinfunction "GND_0") (pintype "passive"))
      (node (ref "J2") (pin "1") (pinfunction "GND_1") (pintype "passive"))
      (node (ref "JP1") (pin "0") (pinfunction "0_0") (pintype "passive"))
      (node (ref "JP1") (pin "1") (pinfunction "GND_1") (pintype "passive"))
      (node (ref "JP1") (pin "10") (pinfunction "GND_10") (pintype "passive"))
      (node (ref "JP1") (pin "2") (pinfunction "GND_2") (pintype "passive"))
      (node (ref "NTC1") (pin "2") (pinfunction "2_2") (pintype "passive"))
      (node (ref "NTC2") (pin "2") (pinfunction "2_2") (pintype "passive"))
      (node (ref "Q3") (pin "6") (pinfunction "S2_6") (pintype "passive"))
      (node (ref "Q3") (pin "7") (pinfunction "S2_7") (pintype "passive"))
      (node (ref "Q3") (pin "8") (pinfunction "S2_8") (pintype "passive"))
      (node (ref "R1") (pin "2") (pinfunction "2_2") (pintype "passive"))
      (node (ref "R10") (pin "2") (pinfunction "2_2") (pintype "passive"))
      (node (ref "R16") (pin "1") (pinfunction "1_1") (pintype "passive"))
      (node (ref "R17") (pin "1") (pinfunction "1_1") (pintype "passive"))
      (node (ref "R32") (pin "1") (pinfunction "1_1") (pintype "passive"))
      (node (ref "R37") (pin "1") (pinfunction "1_1") (pintype "passive"))
      (node (ref "R38") (pin "1") (pinfunction "1_1") (pintype "passive"))
      (node (ref "R5") (pin "2") (pinfunction "2_2") (pintype "passive"))
      (node (ref "R6") (pin "2") (pinfunction "2_2") (pintype "passive"))
      (node (ref "R7") (pin "2") (pinfunction "2_2") (pintype "passive"))
      (node (ref "R8") (pin "2") (pinfunction "2_2") (pintype "passive"))
      (node (ref "SW1") (pin "0") (pinfunction "0_0") (pintype "passive"))
      (node (ref "SW1") (pin "2") (pinfunction "2_2") (pintype "passive"))
      (node (ref "U1") (pin "2") (pinfunction "GND_2") (pintype "passive"))
      (node (ref "U2") (pin "10") (pinfunction "PGND_10") (pintype "passive"))
      (node (ref "U2") (pin "43") (pinfunction "AGND_43") (pintype "passive"))
      (node (ref "U2") (pin "65") (pinfunction "EGND_65") (pintype "passive"))
      (node (ref "U4") (pin "12") (pinfunction "VSS_12") (pintype "bidirectional"))
    )
    (net (code "52") (name "IGND") (class "Default")
      (node (ref "R38") (pin "2") (pinfunction "2_2") (pintype "passive"))
      (node (ref "U2") (pin "44") (pinfunction "IGND_44") (pintype "passive"))
    )
    (net (code "53") (name "ISENSE") (class "Default")
      (node (ref "R36") (pin "2") (pinfunction "2_2") (pintype "passive"))
      (node (ref "U2") (pin "45") (pinfunction "ISENSE_45") (pintype "passive"))
    )
    (net (code "54") (name "Net-(C16-Pad1)") (class "Default")
      (node (ref "C16") (pin "1") (pinfunction "1_1") (pintype "passive"))
      (node (ref "C9") (pin "2") (pinfunction "2_2") (pintype "passive"))
      (node (ref "R11") (pin "2") (pinfunction "2_2") (pintype "passive"))
      (node (ref "R17") (pin "2") (pinfunction "2_2") (pintype "passive"))
    )
    (net (code "55") (name "Net-(D1-K)") (class "Default")
      (node (ref "C2") (pin "2") (pinfunction "2_2") (pintype "passive"))
      (node (ref "D1") (pin "2") (pinfunction "K_2") (pintype "passive"))
      (node (ref "R4") (pin "1") (pinfunction "1_1") (pintype "passive"))
      (node (ref "U1") (pin "5") (pinfunction "VDD_5") (pintype "passive"))
    )
    (net (code "56") (name "Net-(D2-PadK)") (class "Default")
      (node (ref "D2") (pin "K") (pinfunction "K_K") (pintype "passive"))
      (node (ref "R11") (pin "1") (pinfunction "1_1") (pintype "passive"))
      (node (ref "R14") (pin "2") (pinfunction "2_2") (pintype "passive"))
    )
    (net (code "57") (name "Net-(D6-PadA)") (class "Default")
      (node (ref "D6") (pin "A") (pinfunction "A_A") (pintype "passive"))
      (node (ref "R28") (pin "2") (pinfunction "2_2") (pintype "passive"))
    )
    (net (code "58") (name "Net-(D7-PadA)") (class "Default")
      (node (ref "D7") (pin "A") (pinfunction "A_A") (pintype "passive"))
      (node (ref "R31") (pin "2") (pinfunction "2_2") (pintype "passive"))
    )
    (net (code "59") (name "Net-(D8-PadA)") (class "Default")
      (node (ref "D8") (pin "A") (pinfunction "A_A") (pintype "passive"))
      (node (ref "R35") (pin "2") (pinfunction "2_2") (pintype "passive"))
    )
    (net (code "60") (name "Net-(Q1-G)") (class "Default")
      (node (ref "Q1") (pin "4") (pinfunction "G_4") (pintype "passive"))
      (node (ref "R25") (pin "1") (pinfunction "1_1") (pintype "passive"))
      (node (ref "R29") (pin "1") (pinfunction "1_1") (pintype "passive"))
    )
    (net (code "61") (name "Net-(Q2-G)") (class "Default")
      (node (ref "Q2") (pin "4") (pinfunction "G_4") (pintype "passive"))
      (node (ref "R26") (pin "1") (pinfunction "1_1") (pintype "passive"))
      (node (ref "R30") (pin "1") (pinfunction "1_1") (pintype "passive"))
    )
    (net (code "62") (name "Net-(Q3-G1)") (class "Default")
      (node (ref "Q3") (pin "4") (pinfunction "G1_4") (pintype "passive"))
      (node (ref "U3") (pin "1") (pinfunction "OD_1") (pintype "passive"))
    )
    (net (code "63") (name "Net-(Q3-G2)") (class "Default")
      (node (ref "Q3") (pin "5") (pinfunction "G2_5") (pintype "passive"))
      (node (ref "U3") (pin "3") (pinfunction "CO_3") (pintype "passive"))
    )
    (net (code "64") (name "Net-(Q4-G)") (class "Default")
      (node (ref "Q4") (pin "4") (pinfunction "G_4") (pintype "passive"))
      (node (ref "R34") (pin "2") (pinfunction "2_2") (pintype "passive"))
    )
    (net (code "65") (name "Net-(Q5-G)") (class "Default")
      (node (ref "Q5") (pin "4") (pinfunction "G_4") (pintype "passive"))
      (node (ref "R33") (pin "1") (pinfunction "1_1") (pintype "passive"))
    )
    (net (code "66") (name "Net-(R18-Pad1)") (class "Default")
      (node (ref "R18") (pin "1") (pinfunction "1_1") (pintype "passive"))
      (node (ref "U5") (pin "1") (pintype "passive"))
    )
    (net (code "67") (name "Net-(R19-Pad1)") (class "Default")
      (node (ref "R19") (pin "1") (pinfunction "1_1") (pintype "passive"))
      (node (ref "U5") (pin "2") (pintype "passive"))
    )
    (net (code "68") (name "Net-(R20-Pad1)") (class "Default")
      (node (ref "R20") (pin "1") (pinfunction "1_1") (pintype "passive"))
      (node (ref "U5") (pin "3") (pintype "passive"))
    )
    (net (code "69") (name "Net-(R21-Pad1)") (class "Default")
      (node (ref "R21") (pin "1") (pinfunction "1_1") (pintype "passive"))
      (node (ref "U5") (pin "4") (pintype "passive"))
    )
    (net (code "70") (name "Net-(R22-Pad1)") (class "Default")
      (node (ref "R22") (pin "1") (pinfunction "1_1") (pintype "passive"))
      (node (ref "U5") (pin "5") (pintype "passive"))
    )
    (net (code "71") (name "Net-(R24-Pad2)") (class "Default")
      (node (ref "R24") (pin "2") (pinfunction "2_2") (pintype "passive"))
      (node (ref "SW1") (pin "1") (pinfunction "1_1") (pintype "passive"))
    )
    (net (code "72") (name "Net-(U2-BST)") (class "Default")
      (node (ref "C15") (pin "1") (pinfunction "1_1") (pintype "passive"))
      (node (ref "U2") (pin "9") (pinfunction "BST_9") (pintype "passive"))
    )
    (net (code "73") (name "Net-(U2-CPN)") (class "Default")
      (node (ref "C26") (pin "1") (pinfunction "1_1") (pintype "passive"))
      (node (ref "U2") (pin "26") (pinfunction "CPN_26") (pintype "passive"))
    )
    (net (code "74") (name "Net-(U2-CPP)") (class "Default")
      (node (ref "C26") (pin "2") (pinfunction "2_2") (pintype "passive"))
      (node (ref "U2") (pin "27") (pinfunction "CPP_27") (pintype "passive"))
    )
    (net (code "75") (name "Net-(U2-OTPMEMVDD)") (class "Default")
      (node (ref "C27") (pin "1") (pinfunction "1_1") (pintype "passive"))
      (node (ref "U2") (pin "28") (pinfunction "OTPMEMVDD_28") (pintype "passive"))
    )
    (net (code "76") (name "Net-(U3-VCC)") (class "Default")
      (node (ref "C31") (pin "1") (pinfunction "1_1") (pintype "passive"))
      (node (ref "R27") (pin "2") (pinfunction "2_2") (pintype "passive"))
      (node (ref "U3") (pin "5") (pinfunction "VCC_5") (pintype "passive"))
    )
    (net (code "77") (name "Net-(U3-VM)") (class "Default")
      (node (ref "R32") (pin "2") (pinfunction "2_2") (pintype "passive"))
      (node (ref "U3") (pin "2") (pinfunction "VM_2") (pintype "passive"))
    )
    (net (code "78") (name "Net-(U4-VDD)") (class "Default")
      (node (ref "C8") (pin "1") (pinfunction "1_1") (pintype "passive"))
      (node (ref "R9") (pin "2") (pinfunction "2_2") (pintype "passive"))
      (node (ref "U4") (pin "5") (pinfunction "VDD_5") (pintype "bidirectional"))
    )
    (net (code "79") (name "SW1") (class "Default")
      (node (ref "C25") (pin "1") (pinfunction "1_1") (pintype "passive"))
      (node (ref "Q1") (pin "5") (pinfunction "D2_5") (pintype "passive"))
      (node (ref "Q1") (pin "6") (pinfunction "D3_6") (pintype "passive"))
      (node (ref "Q1") (pin "7") (pinfunction "D1_7") (pintype "passive"))
      (node (ref "Q1") (pin "8") (pinfunction "D1_8") (pintype "passive"))
      (node (ref "Q1") (pin "9") (pinfunction "D4_9") (pintype "passive"))
      (node (ref "Q5") (pin "5") (pinfunction "D2_5") (pintype "passive"))
      (node (ref "Q5") (pin "6") (pinfunction "D3_6") (pintype "passive"))
      (node (ref "Q5") (pin "7") (pinfunction "D1_7") (pintype "passive"))
      (node (ref "Q5") (pin "8") (pinfunction "D1_8") (pintype "passive"))
      (node (ref "Q5") (pin "9") (pinfunction "D_9") (pintype "passive"))
    )
    (net (code "80") (name "SW2") (class "Default")
      (node (ref "C19") (pin "1") (pinfunction "1_1") (pintype "passive"))
      (node (ref "L2") (pin "2") (pinfunction "2_2") (pintype "passive"))
      (node (ref "Q2") (pin "5") (pinfunction "D2_5") (pintype "passive"))
      (node (ref "Q2") (pin "6") (pinfunction "D3_6") (pintype "passive"))
      (node (ref "Q2") (pin "7") (pinfunction "D1_7") (pintype "passive"))
      (node (ref "Q2") (pin "8") (pinfunction "D1_8") (pintype "passive"))
      (node (ref "Q2") (pin "9") (pinfunction "D4_9") (pintype "passive"))
      (node (ref "Q4") (pin "5") (pinfunction "D2_5") (pintype "passive"))
      (node (ref "Q4") (pin "6") (pinfunction "D3_6") (pintype "passive"))
      (node (ref "Q4") (pin "7") (pinfunction "D1_7") (pintype "passive"))
      (node (ref "Q4") (pin "8") (pinfunction "D1_8") (pintype "passive"))
      (node (ref "Q4") (pin "9") (pinfunction "D_9") (pintype "passive"))
    )
    (net (code "81") (name "UPGATE1") (class "Default")
      (node (ref "R29") (pin "2") (pinfunction "2_2") (pintype "passive"))
      (node (ref "U2") (pin "54") (pinfunction "UPGATE1_54") (pintype "passive"))
    )
    (net (code "82") (name "UPGATE2") (class "Default")
      (node (ref "R30") (pin "2") (pinfunction "2_2") (pintype "passive"))
      (node (ref "U2") (pin "52") (pinfunction "UPGATE2_52") (pintype "passive"))
    )
    (net (code "83") (name "VBRIGE") (class "Default")
      (node (ref "C29") (pin "2") (pinfunction "2_2") (pintype "passive"))
      (node (ref "C30") (pin "2") (pinfunction "2_2") (pintype "passive"))
      (node (ref "Q1") (pin "1") (pinfunction "S_1") (pintype "passive"))
      (node (ref "Q1") (pin "2") (pinfunction "S_2") (pintype "passive"))
      (node (ref "Q1") (pin "3") (pinfunction "S_3") (pintype "passive"))
      (node (ref "Q2") (pin "1") (pinfunction "S_1") (pintype "passive"))
      (node (ref "Q2") (pin "2") (pinfunction "S_2") (pintype "passive"))
      (node (ref "Q2") (pin "3") (pinfunction "S_3") (pintype "passive"))
      (node (ref "R23") (pin "2") (pinfunction "2_2") (pintype "passive"))
      (node (ref "R25") (pin "2") (pinfunction "2_2") (pintype "passive"))
      (node (ref "R26") (pin "2") (pinfunction "2_2") (pintype "passive"))
    )
    (net (code "84") (name "VCC") (class "Default")
      (node (ref "C28") (pin "1") (pinfunction "1_1") (pintype "passive"))
      (node (ref "D3") (pin "K") (pinfunction "K_K") (pintype "passive"))
      (node (ref "R12") (pin "2") (pinfunction "2_2") (pintype "passive"))
      (node (ref "R15") (pin "2") (pinfunction "2_2") (pintype "passive"))
      (node (ref "R9") (pin "1") (pinfunction "1_1") (pintype "passive"))
      (node (ref "U2") (pin "25") (pinfunction "VCC_25") (pintype "passive"))
    )
    (net (code "85") (name "unconnected-(J1-SBU1-PadA8)") (class "Default")
      (node (ref "J1") (pin "A8") (pinfunction "SBU1_A8") (pintype "passive+no_connect"))
    )
    (net (code "86") (name "unconnected-(J1-SBU2-PadB8)") (class "Default")
      (node (ref "J1") (pin "B8") (pinfunction "SBU2_B8") (pintype "passive+no_connect"))
    )
    (net (code "87") (name "unconnected-(JP1-D--Pad7)") (class "Default")
      (node (ref "JP1") (pin "7") (pinfunction "D-_7") (pintype "passive+no_connect"))
    )
    (net (code "88") (name "unconnected-(JP1-D1+-Pad3)") (class "Default")
      (node (ref "JP1") (pin "3") (pinfunction "D1+_3") (pintype "passive+no_connect"))
    )
    (net (code "89") (name "unconnected-(JP1-D1--Pad4)") (class "Default")
      (node (ref "JP1") (pin "4") (pinfunction "D1-_4") (pintype "passive+no_connect"))
    )
    (net (code "90") (name "unconnected-(Q3-D1D2-Pad0)") (class "Default")
      (node (ref "Q3") (pin "0") (pinfunction "D1D2_0") (pintype "passive+no_connect"))
    )
    (net (code "91") (name "unconnected-(U1-GATE-Pad3)") (class "Default")
      (node (ref "U1") (pin "3") (pinfunction "GATE_3") (pintype "passive"))
    )
    (net (code "92") (name "unconnected-(U1-NC-Pad4)") (class "Default")
      (node (ref "U1") (pin "4") (pinfunction "NC_4") (pintype "passive"))
    )
    (net (code "93") (name "unconnected-(U2-AUXDRV1-Pad51)") (class "Default")
      (node (ref "U2") (pin "51") (pinfunction "AUXDRV1_51") (pintype "passive+no_connect"))
    )
    (net (code "94") (name "unconnected-(U2-AUXDRV2-Pad50)") (class "Default")
      (node (ref "U2") (pin "50") (pinfunction "AUXDRV2_50") (pintype "passive+no_connect"))
    )
    (net (code "95") (name "unconnected-(U2-AUXDRV3-Pad49)") (class "Default")
      (node (ref "U2") (pin "49") (pinfunction "AUXDRV3_49") (pintype "passive+no_connect"))
    )
    (net (code "96") (name "unconnected-(U2-NC-Pad15)") (class "Default")
      (node (ref "U2") (pin "15") (pinfunction "NC_15") (pintype "passive+no_connect"))
    )
    (net (code "97") (name "unconnected-(U2-NC-Pad16)") (class "Default")
      (node (ref "U2") (pin "16") (pinfunction "NC_16") (pintype "passive+no_connect"))
    )
    (net (code "98") (name "unconnected-(U3-NC-Pad4)") (class "Default")
      (node (ref "U3") (pin "4") (pinfunction "NC_4") (pintype "passive+no_connect"))
    )
    (net (code "99") (name "unconnected-(U4-PA5{slash}RSTB{slash}VPP-Pad8)") (class "Default")
      (node (ref "U4") (pin "8") (pinfunction "PA5/RSTB/VPP_8") (pintype "bidirectional+no_connect"))
    )
  )
)
